# SCH_Fetch_Execution_Counter_2021-10-10.net
KiCad netlist of a schematic drawn in EasyEDA
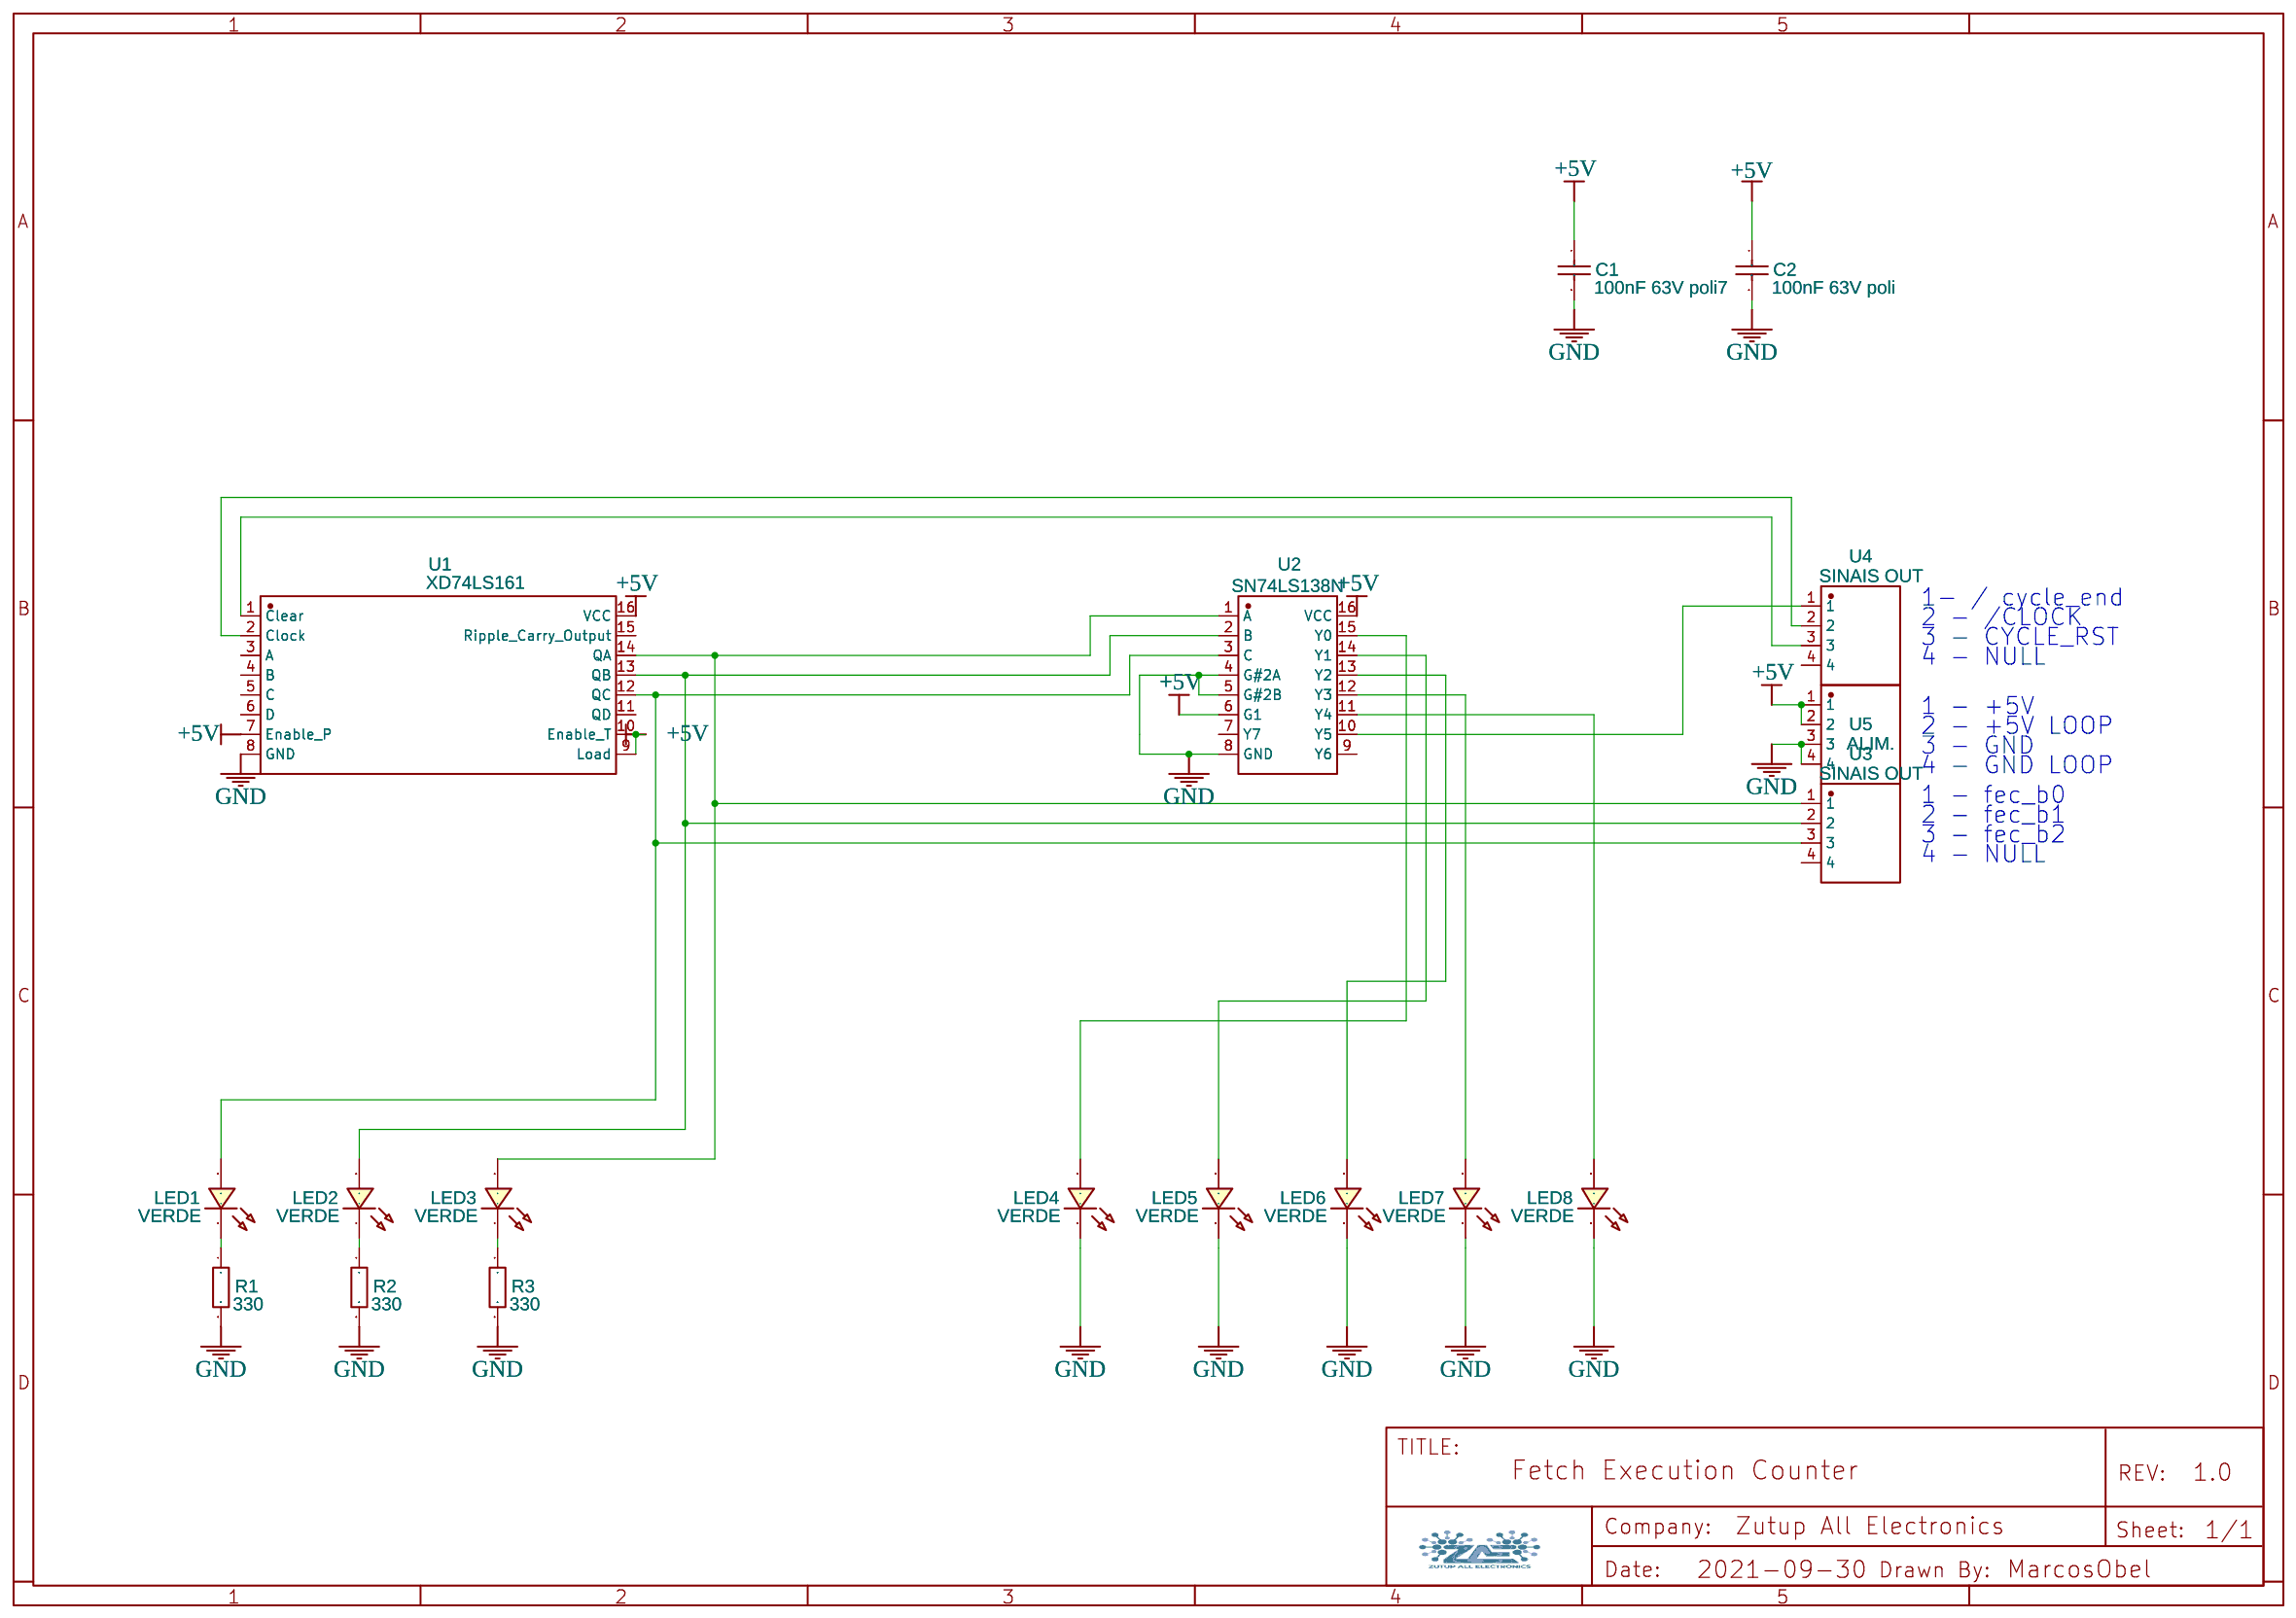
[diagram p0: schematic sheet]

(export (version "E")
  (design (tool "Eeschema 10.0.6"))
  (components
    (comp (ref "C1")
      (value "100nF 63V poli7")
      (fields
        (field (name "BOM_Manufacturer Part") "SR305C105KAR")
        (field (name "BOM_Supplier Part") "C444741")
      )
      (libsource (lib "") (part "SR305C105KAR"))
    )
    (comp (ref "C2")
      (value "100nF 63V poli")
      (fields
        (field (name "BOM_Manufacturer Part") "SR305C105KAR")
        (field (name "BOM_Supplier Part") "C444741")
      )
      (libsource (lib "") (part "SR305C105KAR"))
    )
    (comp (ref "LED1")
      (value "VERDE")
      (fields (field (name "BOM_Manufacturer Part") "264-7GD") (field (name "BOM_Supplier Part") "C605465"))
      (libsource (lib "") (part "264-7GD"))
    )
    (comp (ref "LED2")
      (value "VERDE")
      (fields (field (name "BOM_Manufacturer Part") "264-7GD") (field (name "BOM_Supplier Part") "C605465"))
      (libsource (lib "") (part "264-7GD"))
    )
    (comp (ref "LED3")
      (value "VERDE")
      (fields (field (name "BOM_Manufacturer Part") "264-7GD") (field (name "BOM_Supplier Part") "C605465"))
      (libsource (lib "") (part "264-7GD"))
    )
    (comp (ref "LED4")
      (value "VERDE")
      (fields (field (name "BOM_Manufacturer Part") "264-7GD") (field (name "BOM_Supplier Part") "C605465"))
      (libsource (lib "") (part "264-7GD"))
    )
    (comp (ref "LED5")
      (value "VERDE")
      (fields (field (name "BOM_Manufacturer Part") "264-7GD") (field (name "BOM_Supplier Part") "C605465"))
      (libsource (lib "") (part "264-7GD"))
    )
    (comp (ref "LED6")
      (value "VERDE")
      (fields (field (name "BOM_Manufacturer Part") "264-7GD") (field (name "BOM_Supplier Part") "C605465"))
      (libsource (lib "") (part "264-7GD"))
    )
    (comp (ref "LED7")
      (value "VERDE")
      (fields (field (name "BOM_Manufacturer Part") "264-7GD") (field (name "BOM_Supplier Part") "C605465"))
      (libsource (lib "") (part "264-7GD"))
    )
    (comp (ref "LED8")
      (value "VERDE")
      (fields (field (name "BOM_Manufacturer Part") "264-7GD") (field (name "BOM_Supplier Part") "C605465"))
      (libsource (lib "") (part "264-7GD"))
    )
    (comp (ref "R1")
      (value "330")
      (fields
        (field (name "BOM_Manufacturer Part") "CFR02SJ0823A10")
        (field (name "BOM_Supplier Part") "C69876")
      )
      (libsource (lib "") (part "CFR02SJ0823A10"))
    )
    (comp (ref "R2")
      (value "330")
      (fields
        (field (name "BOM_Manufacturer Part") "CFR02SJ0823A10")
        (field (name "BOM_Supplier Part") "C69876")
      )
      (libsource (lib "") (part "CFR02SJ0823A10"))
    )
    (comp (ref "R3")
      (value "330")
      (fields
        (field (name "BOM_Manufacturer Part") "CFR02SJ0823A10")
        (field (name "BOM_Supplier Part") "C69876")
      )
      (libsource (lib "") (part "CFR02SJ0823A10"))
    )
    (comp (ref "U1")
      (value "XD74LS161")
      (fields (field (name "BOM_Supplier Part") "C609766"))
      (libsource (lib "") (part "XD74LS161"))
    )
    (comp (ref "U2")
      (value "SN74LS138N")
      (fields (field (name "BOM_Supplier Part") "C352964"))
      (libsource (lib "") (part "SN74LS138N"))
    )
    (comp (ref "U3")
      (value "SINAIS OUT")
      (fields (field (name "BOM_Manufacturer Part") "171825-4") (field (name "BOM_Supplier Part") "C210162"))
      (libsource (lib "") (part "171825-4"))
    )
    (comp (ref "U4")
      (value "SINAIS OUT")
      (fields (field (name "BOM_Manufacturer Part") "171825-4") (field (name "BOM_Supplier Part") "C210162"))
      (libsource (lib "") (part "171825-4"))
    )
    (comp (ref "U5")
      (value "ALIM.")
      (fields (field (name "BOM_Manufacturer Part") "171825-4") (field (name "BOM_Supplier Part") "C210162"))
      (libsource (lib "") (part "171825-4"))
    )
  )
  (nets
    (net (code "1") (name "+5V") (class "Default")
      (node (ref "C1") (pin "1") (pinfunction "1_1") (pintype "input"))
      (node (ref "C2") (pin "1") (pinfunction "1_1") (pintype "input"))
      (node (ref "U1") (pin "10") (pinfunction "Enable_T_10") (pintype "unspecified"))
      (node (ref "U1") (pin "16") (pinfunction "VCC_16") (pintype "unspecified"))
      (node (ref "U1") (pin "7") (pinfunction "Enable_P_7") (pintype "unspecified"))
      (node (ref "U1") (pin "9") (pinfunction "Load_9") (pintype "unspecified"))
      (node (ref "U2") (pin "16") (pinfunction "VCC_16") (pintype "unspecified"))
      (node (ref "U2") (pin "6") (pinfunction "G1_6") (pintype "unspecified"))
      (node (ref "U5") (pin "1") (pinfunction "1_1") (pintype "unspecified"))
      (node (ref "U5") (pin "2") (pinfunction "2_2") (pintype "unspecified"))
    )
    (net (code "2") (name "GND") (class "Default")
      (node (ref "C1") (pin "2") (pinfunction "2_2") (pintype "input"))
      (node (ref "C2") (pin "2") (pinfunction "2_2") (pintype "input"))
      (node (ref "LED4") (pin "1") (pinfunction "-_1") (pintype "unspecified"))
      (node (ref "LED5") (pin "1") (pinfunction "-_1") (pintype "unspecified"))
      (node (ref "LED6") (pin "1") (pinfunction "-_1") (pintype "unspecified"))
      (node (ref "LED7") (pin "1") (pinfunction "-_1") (pintype "unspecified"))
      (node (ref "LED8") (pin "1") (pinfunction "-_1") (pintype "unspecified"))
      (node (ref "R1") (pin "2") (pinfunction "2_2") (pintype "input"))
      (node (ref "R2") (pin "2") (pinfunction "2_2") (pintype "input"))
      (node (ref "R3") (pin "2") (pinfunction "2_2") (pintype "input"))
      (node (ref "U1") (pin "8") (pinfunction "GND_8") (pintype "unspecified"))
      (node (ref "U2") (pin "4") (pinfunction "G#2A_4") (pintype "unspecified"))
      (node (ref "U2") (pin "5") (pinfunction "G#2B_5") (pintype "unspecified"))
      (node (ref "U2") (pin "8") (pinfunction "GND_8") (pintype "unspecified"))
      (node (ref "U5") (pin "3") (pinfunction "3_3") (pintype "unspecified"))
      (node (ref "U5") (pin "4") (pinfunction "4_4") (pintype "unspecified"))
    )
    (net (code "3") (name "Net-(LED1-+)") (class "Default")
      (node (ref "LED1") (pin "2") (pinfunction "+_2") (pintype "unspecified"))
      (node (ref "U1") (pin "12") (pinfunction "QC_12") (pintype "unspecified"))
      (node (ref "U2") (pin "3") (pinfunction "C_3") (pintype "unspecified"))
      (node (ref "U3") (pin "3") (pinfunction "3_3") (pintype "unspecified"))
    )
    (net (code "4") (name "Net-(LED1--)") (class "Default")
      (node (ref "LED1") (pin "1") (pinfunction "-_1") (pintype "unspecified"))
      (node (ref "R1") (pin "1") (pinfunction "1_1") (pintype "input"))
    )
    (net (code "5") (name "Net-(LED2-+)") (class "Default")
      (node (ref "LED2") (pin "2") (pinfunction "+_2") (pintype "unspecified"))
      (node (ref "U1") (pin "13") (pinfunction "QB_13") (pintype "unspecified"))
      (node (ref "U2") (pin "2") (pinfunction "B_2") (pintype "unspecified"))
      (node (ref "U3") (pin "2") (pinfunction "2_2") (pintype "unspecified"))
    )
    (net (code "6") (name "Net-(LED2--)") (class "Default")
      (node (ref "LED2") (pin "1") (pinfunction "-_1") (pintype "unspecified"))
      (node (ref "R2") (pin "1") (pinfunction "1_1") (pintype "input"))
    )
    (net (code "7") (name "Net-(LED3-+)") (class "Default")
      (node (ref "LED3") (pin "2") (pinfunction "+_2") (pintype "unspecified"))
      (node (ref "U1") (pin "14") (pinfunction "QA_14") (pintype "unspecified"))
      (node (ref "U2") (pin "1") (pinfunction "A_1") (pintype "unspecified"))
      (node (ref "U3") (pin "1") (pinfunction "1_1") (pintype "unspecified"))
    )
    (net (code "8") (name "Net-(LED3--)") (class "Default")
      (node (ref "LED3") (pin "1") (pinfunction "-_1") (pintype "unspecified"))
      (node (ref "R3") (pin "1") (pinfunction "1_1") (pintype "input"))
    )
    (net (code "9") (name "Net-(LED4-+)") (class "Default")
      (node (ref "LED4") (pin "2") (pinfunction "+_2") (pintype "unspecified"))
      (node (ref "U2") (pin "15") (pinfunction "Y0_15") (pintype "unspecified"))
    )
    (net (code "10") (name "Net-(LED5-+)") (class "Default")
      (node (ref "LED5") (pin "2") (pinfunction "+_2") (pintype "unspecified"))
      (node (ref "U2") (pin "14") (pinfunction "Y1_14") (pintype "unspecified"))
    )
    (net (code "11") (name "Net-(LED6-+)") (class "Default")
      (node (ref "LED6") (pin "2") (pinfunction "+_2") (pintype "unspecified"))
      (node (ref "U2") (pin "13") (pinfunction "Y2_13") (pintype "unspecified"))
    )
    (net (code "12") (name "Net-(LED7-+)") (class "Default")
      (node (ref "LED7") (pin "2") (pinfunction "+_2") (pintype "unspecified"))
      (node (ref "U2") (pin "12") (pinfunction "Y3_12") (pintype "unspecified"))
    )
    (net (code "13") (name "Net-(LED8-+)") (class "Default")
      (node (ref "LED8") (pin "2") (pinfunction "+_2") (pintype "unspecified"))
      (node (ref "U2") (pin "11") (pinfunction "Y4_11") (pintype "unspecified"))
    )
    (net (code "14") (name "Net-(U1-Clear)") (class "Default")
      (node (ref "U1") (pin "1") (pinfunction "Clear_1") (pintype "unspecified"))
      (node (ref "U4") (pin "3") (pinfunction "3_3") (pintype "unspecified"))
    )
    (net (code "15") (name "Net-(U1-Clock)") (class "Default")
      (node (ref "U1") (pin "2") (pinfunction "Clock_2") (pintype "unspecified"))
      (node (ref "U4") (pin "2") (pinfunction "2_2") (pintype "unspecified"))
    )
    (net (code "16") (name "Net-(U2-Y5)") (class "Default")
      (node (ref "U2") (pin "10") (pinfunction "Y5_10") (pintype "unspecified"))
      (node (ref "U4") (pin "1") (pinfunction "1_1") (pintype "unspecified"))
    )
    (net (code "17") (name "unconnected-(U1-A-Pad3)") (class "Default")
      (node (ref "U1") (pin "3") (pinfunction "A_3") (pintype "unspecified"))
    )
    (net (code "18") (name "unconnected-(U1-B-Pad4)") (class "Default")
      (node (ref "U1") (pin "4") (pinfunction "B_4") (pintype "unspecified"))
    )
    (net (code "19") (name "unconnected-(U1-C-Pad5)") (class "Default")
      (node (ref "U1") (pin "5") (pinfunction "C_5") (pintype "unspecified"))
    )
    (net (code "20") (name "unconnected-(U1-D-Pad6)") (class "Default")
      (node (ref "U1") (pin "6") (pinfunction "D_6") (pintype "unspecified"))
    )
    (net (code "21") (name "unconnected-(U1-QD-Pad11)") (class "Default")
      (node (ref "U1") (pin "11") (pinfunction "QD_11") (pintype "unspecified"))
    )
    (net (code "22") (name "unconnected-(U1-Ripple_Carry_Output-Pad15)") (class "Default")
      (node (ref "U1") (pin "15") (pinfunction "Ripple_Carry_Output_15") (pintype "unspecified"))
    )
    (net (code "23") (name "unconnected-(U2-Y6-Pad9)") (class "Default")
      (node (ref "U2") (pin "9") (pinfunction "Y6_9") (pintype "unspecified"))
    )
    (net (code "24") (name "unconnected-(U2-Y7-Pad7)") (class "Default")
      (node (ref "U2") (pin "7") (pinfunction "Y7_7") (pintype "unspecified"))
    )
    (net (code "25") (name "unconnected-(U3-Pad4)") (class "Default")
      (node (ref "U3") (pin "4") (pinfunction "4_4") (pintype "unspecified"))
    )
    (net (code "26") (name "unconnected-(U4-Pad4)") (class "Default")
      (node (ref "U4") (pin "4") (pinfunction "4_4") (pintype "unspecified"))
    )
  )
)
